# lightSoakV1-InAmp-piggyback-sch.net
KiCad netlist of a schematic drawn in Altium Designer
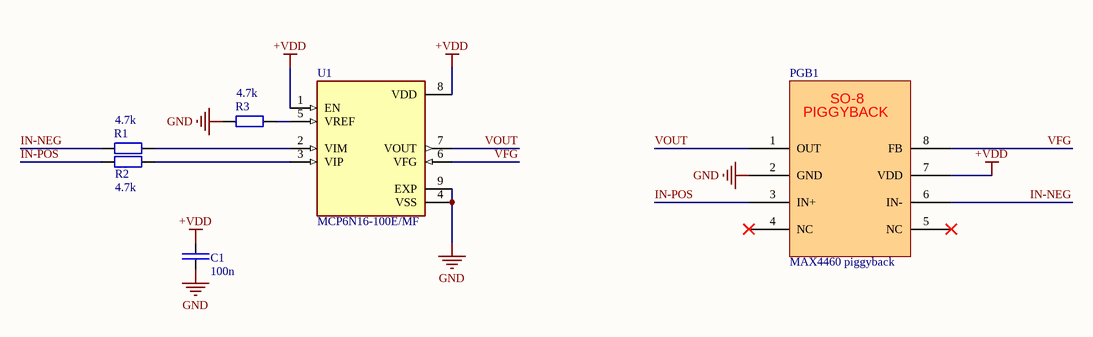
[diagram p0: lightSoakV1-InAmp-piggyback-sch.SchDoc]

(export (version "E")
  (design (tool "Eeschema 10.0.6"))
  (components
    (comp (ref "C1")
      (value "100n")
      (footprint "Passives:FPR_0402_C_R0")
      (description "Capacitor - generic SMD")
      (fields (field (name "Comment") "PN_C_100n"))
      (libsource (lib "Passives") (part "C"))
    )
    (comp (ref "PGB1")
      (value "MAX4460 piggyback")
      (footprint "SO-8 piggyback")
      (libsource (lib "MAX4460-piggyback-schlib") (part "MAX4460 piggyback"))
    )
    (comp (ref "R1")
      (value "4.7k")
      (footprint "Passives:FPR_0402_R_R0")
      (description "Resistor - generic SMD")
      (fields (field (name "Comment") "PN_R_4k7"))
      (libsource (lib "Passives") (part "R"))
    )
    (comp (ref "R2")
      (value "4.7k")
      (footprint "Passives:FPR_0402_R_R0")
      (description "Resistor - generic SMD")
      (fields (field (name "Comment") "PN_R_4k7"))
      (libsource (lib "Passives") (part "R"))
    )
    (comp (ref "R3")
      (value "4.7k")
      (footprint "Passives:FPR_0402_R_R0")
      (description "Resistor - generic SMD")
      (fields (field (name "Comment") "PN_R_4k7"))
      (libsource (lib "Passives") (part "R"))
    )
    (comp (ref "U1")
      (value "MCP6N16-100E/MF")
      (footprint "SON65P300X300X100-9N")
      (description "Instrumentation Amplifier 1 Circuit Rail-to-Rail 8-DFN-EP (3x3)")
      (fields (field (name "MF") "Microchip"))
      (libsource (lib "MCP6N16-100E_MF") (part "MCP6N16-100E/MF"))
    )
  )
  (nets
    (net (code "1") (name "+VDD") (class "Default")
      (node (ref "C1") (pin "2") (pinfunction "2_2") (pintype "passive"))
      (node (ref "PGB1") (pin "7") (pinfunction "VDD_7") (pintype "passive"))
      (node (ref "U1") (pin "1") (pinfunction "EN_1") (pintype "input"))
      (node (ref "U1") (pin "8") (pinfunction "VDD_8") (pintype "power_in"))
    )
    (net (code "2") (name "/IN-NEG") (class "Default")
      (node (ref "PGB1") (pin "6") (pinfunction "IN-_6") (pintype "passive"))
      (node (ref "R1") (pin "2") (pinfunction "2_2") (pintype "passive"))
    )
    (net (code "3") (name "/IN-POS") (class "Default")
      (node (ref "PGB1") (pin "3") (pinfunction "IN+_3") (pintype "passive"))
      (node (ref "R2") (pin "2") (pinfunction "2_2") (pintype "passive"))
    )
    (net (code "4") (name "/VFG") (class "Default")
      (node (ref "PGB1") (pin "8") (pinfunction "FB_8") (pintype "passive"))
      (node (ref "U1") (pin "6") (pinfunction "VFG_6") (pintype "input"))
    )
    (net (code "5") (name "/VOUT") (class "Default")
      (node (ref "PGB1") (pin "1") (pinfunction "OUT_1") (pintype "passive"))
      (node (ref "U1") (pin "7") (pinfunction "VOUT_7") (pintype "output"))
    )
    (net (code "6") (name "GND") (class "Default")
      (node (ref "C1") (pin "1") (pinfunction "1_1") (pintype "passive"))
      (node (ref "PGB1") (pin "2") (pinfunction "GND_2") (pintype "passive"))
      (node (ref "R3") (pin "2") (pinfunction "2_2") (pintype "passive"))
      (node (ref "U1") (pin "4") (pinfunction "VSS_4") (pintype "power_in"))
      (node (ref "U1") (pin "9") (pinfunction "EXP_9") (pintype "power_in"))
    )
    (net (code "7") (name "Net-(U1-VIM)") (class "Default")
      (node (ref "R1") (pin "1") (pinfunction "1_1") (pintype "passive"))
      (node (ref "U1") (pin "2") (pinfunction "VIM_2") (pintype "input"))
    )
    (net (code "8") (name "Net-(U1-VIP)") (class "Default")
      (node (ref "R2") (pin "1") (pinfunction "1_1") (pintype "passive"))
      (node (ref "U1") (pin "3") (pinfunction "VIP_3") (pintype "input"))
    )
    (net (code "9") (name "Net-(U1-VREF)") (class "Default")
      (node (ref "R3") (pin "1") (pinfunction "1_1") (pintype "passive"))
      (node (ref "U1") (pin "5") (pinfunction "VREF_5") (pintype "input"))
    )
    (net (code "10") (name "unconnected-(PGB1-NC-Pad4)") (class "Default")
      (node (ref "PGB1") (pin "4") (pinfunction "NC_4") (pintype "passive+no_connect"))
    )
    (net (code "11") (name "unconnected-(PGB1-NC-Pad5)") (class "Default")
      (node (ref "PGB1") (pin "5") (pinfunction "NC_5") (pintype "passive+no_connect"))
    )
  )
)
